# de0_expansion.net
KiCad netlist of a schematic drawn in EAGLE
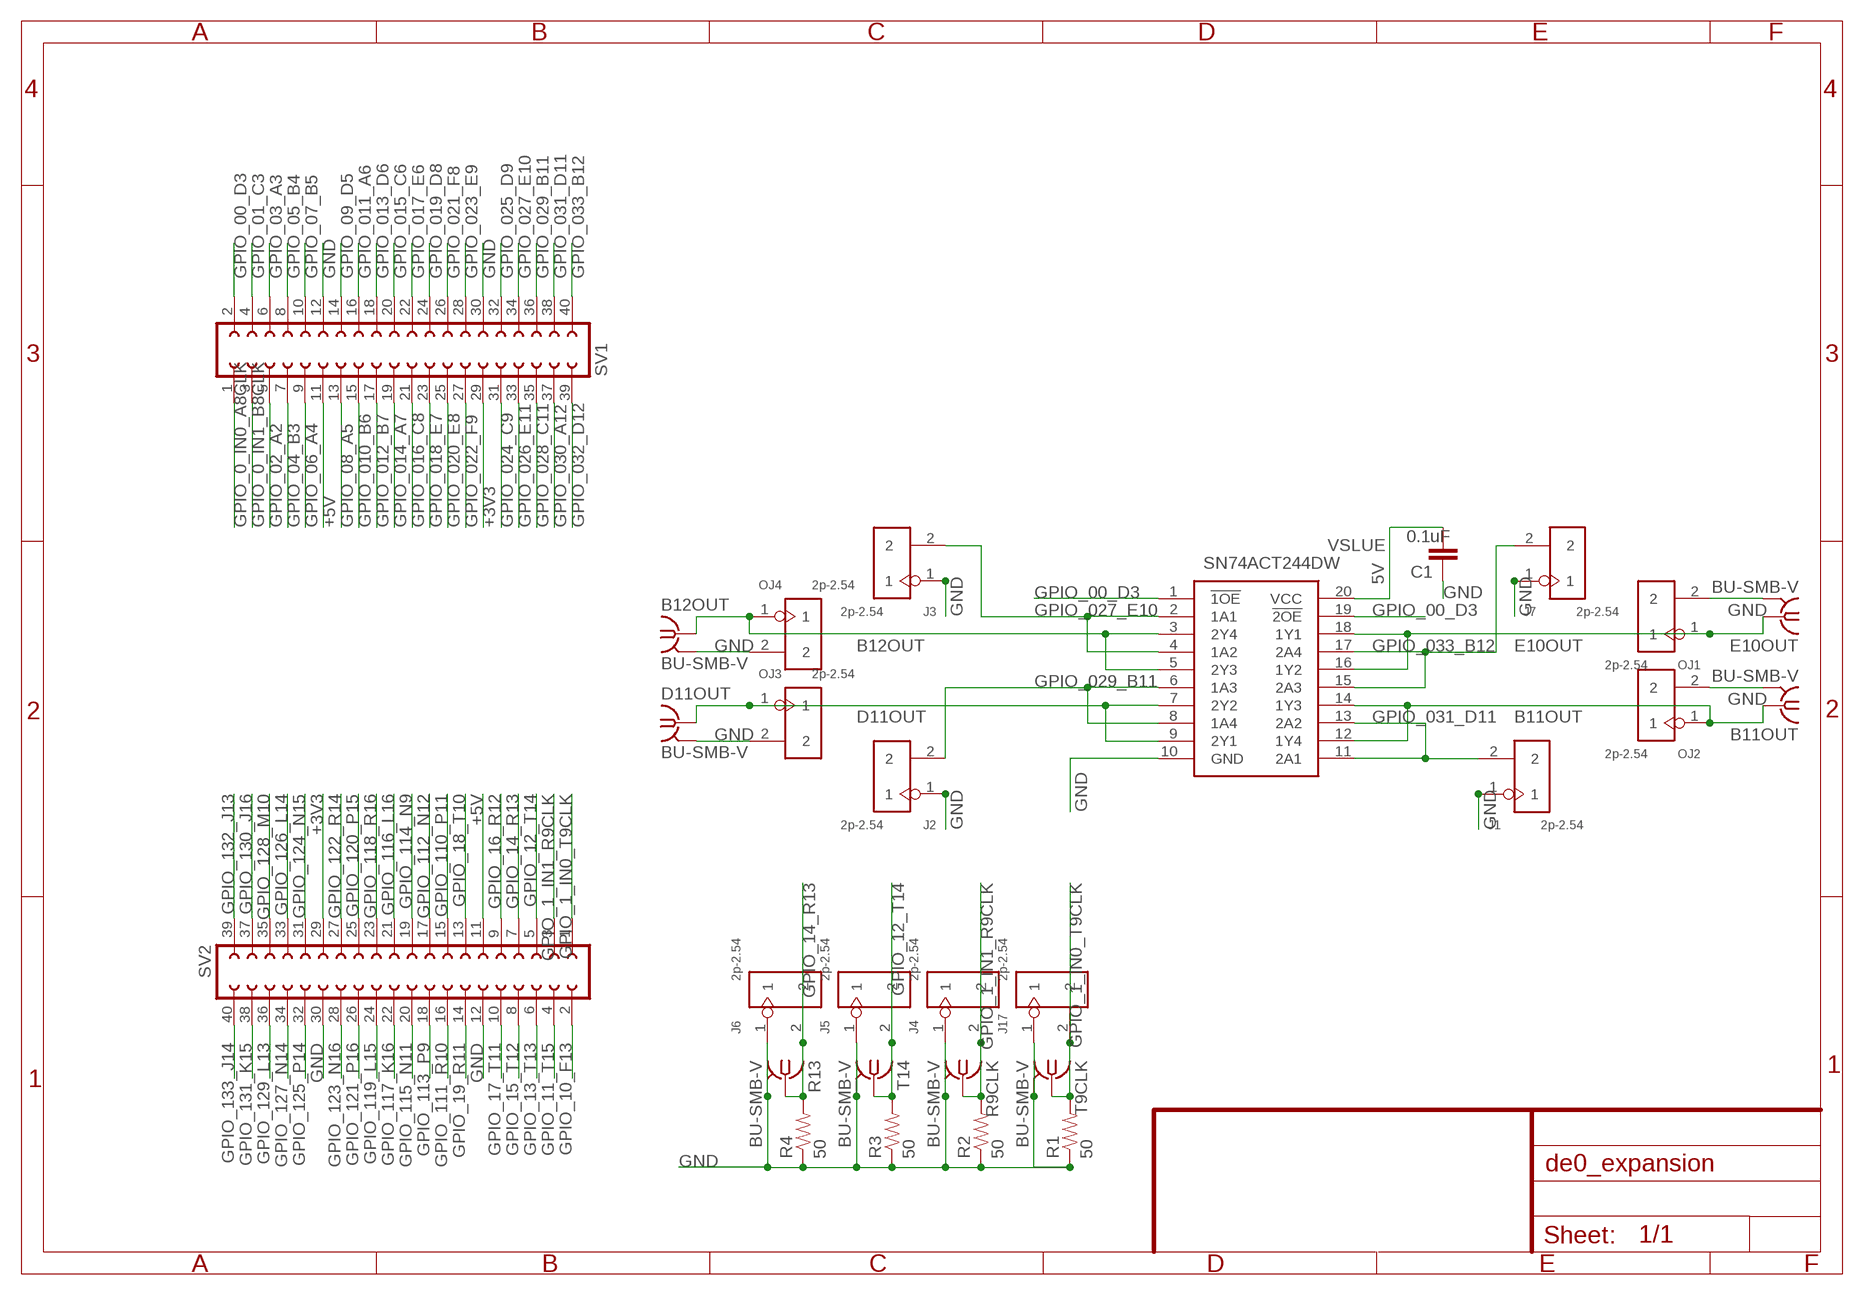
[diagram p0: schematic, sheet 1]

(export (version "E")
  (design (tool "Eeschema 10.0.6"))
  (components
    (comp (ref "B11OUT")
      (value "BU-SMB-V")
      (footprint "eagle-import:BU-SMB-V")
      (libsource (lib "eagle-import") (part "BU-SMB-V"))
    )
    (comp (ref "B12OUT")
      (value "BU-SMB-V")
      (footprint "eagle-import:BU-SMB-V")
      (libsource (lib "eagle-import") (part "BU-SMB-V"))
    )
    (comp (ref "C1")
      (value "0.1uF")
      (footprint "eagle-import:0805")
      (libsource (lib "eagle-import") (part "CAP0805"))
    )
    (comp (ref "D11OUT")
      (value "BU-SMB-V")
      (footprint "eagle-import:BU-SMB-V")
      (libsource (lib "eagle-import") (part "BU-SMB-V"))
    )
    (comp (ref "E10OUT")
      (value "BU-SMB-V")
      (footprint "eagle-import:BU-SMB-V")
      (libsource (lib "eagle-import") (part "BU-SMB-V"))
    )
    (comp (ref "J1")
      (value "2p-2.54")
      (footprint "eagle-import:H2-2.54")
      (fields (field (name "MPN") "P125-1102A0BS116A1"))
      (libsource (lib "eagle-import") (part "DIP-BLACK-MALE-HEADER-VERT(2P-2.54)"))
    )
    (comp (ref "J2")
      (value "2p-2.54")
      (footprint "eagle-import:H2-2.54")
      (fields (field (name "MPN") "P125-1102A0BS116A1"))
      (libsource (lib "eagle-import") (part "DIP-BLACK-MALE-HEADER-VERT(2P-2.54)"))
    )
    (comp (ref "J3")
      (value "2p-2.54")
      (footprint "eagle-import:H2-2.54")
      (fields (field (name "MPN") "P125-1102A0BS116A1"))
      (libsource (lib "eagle-import") (part "DIP-BLACK-MALE-HEADER-VERT(2P-2.54)"))
    )
    (comp (ref "J4")
      (value "2p-2.54")
      (footprint "eagle-import:H2-2.54")
      (fields (field (name "MPN") "P125-1102A0BS116A1"))
      (libsource (lib "eagle-import") (part "DIP-BLACK-MALE-HEADER-VERT(2P-2.54)"))
    )
    (comp (ref "J5")
      (value "2p-2.54")
      (footprint "eagle-import:H2-2.54")
      (fields (field (name "MPN") "P125-1102A0BS116A1"))
      (libsource (lib "eagle-import") (part "DIP-BLACK-MALE-HEADER-VERT(2P-2.54)"))
    )
    (comp (ref "J6")
      (value "2p-2.54")
      (footprint "eagle-import:H2-2.54")
      (fields (field (name "MPN") "P125-1102A0BS116A1"))
      (libsource (lib "eagle-import") (part "DIP-BLACK-MALE-HEADER-VERT(2P-2.54)"))
    )
    (comp (ref "J7")
      (value "2p-2.54")
      (footprint "eagle-import:H2-2.54")
      (fields (field (name "MPN") "P125-1102A0BS116A1"))
      (libsource (lib "eagle-import") (part "DIP-BLACK-MALE-HEADER-VERT(2P-2.54)"))
    )
    (comp (ref "J17")
      (value "2p-2.54")
      (footprint "eagle-import:H2-2.54")
      (fields (field (name "MPN") "P125-1102A0BS116A1"))
      (libsource (lib "eagle-import") (part "DIP-BLACK-MALE-HEADER-VERT(2P-2.54)"))
    )
    (comp (ref "OJ1")
      (value "2p-2.54")
      (footprint "eagle-import:H2-2.54")
      (fields (field (name "MPN") "P125-1102A0BS116A1"))
      (libsource (lib "eagle-import") (part "DIP-BLACK-MALE-HEADER-VERT(2P-2.54)"))
    )
    (comp (ref "OJ2")
      (value "2p-2.54")
      (footprint "eagle-import:H2-2.54")
      (fields (field (name "MPN") "P125-1102A0BS116A1"))
      (libsource (lib "eagle-import") (part "DIP-BLACK-MALE-HEADER-VERT(2P-2.54)"))
    )
    (comp (ref "OJ3")
      (value "2p-2.54")
      (footprint "eagle-import:H2-2.54")
      (fields (field (name "MPN") "P125-1102A0BS116A1"))
      (libsource (lib "eagle-import") (part "DIP-BLACK-MALE-HEADER-VERT(2P-2.54)"))
    )
    (comp (ref "OJ4")
      (value "2p-2.54")
      (footprint "eagle-import:H2-2.54")
      (fields (field (name "MPN") "P125-1102A0BS116A1"))
      (libsource (lib "eagle-import") (part "DIP-BLACK-MALE-HEADER-VERT(2P-2.54)"))
    )
    (comp (ref "R1")
      (value "50")
      (footprint "eagle-import:AXIAL-0.3")
      (libsource (lib "eagle-import") (part "RESISTORAXIAL-0.3"))
    )
    (comp (ref "R2")
      (value "50")
      (footprint "eagle-import:AXIAL-0.3")
      (libsource (lib "eagle-import") (part "RESISTORAXIAL-0.3"))
    )
    (comp (ref "R3")
      (value "50")
      (footprint "eagle-import:AXIAL-0.3")
      (libsource (lib "eagle-import") (part "RESISTORAXIAL-0.3"))
    )
    (comp (ref "R4")
      (value "50")
      (footprint "eagle-import:AXIAL-0.3")
      (libsource (lib "eagle-import") (part "RESISTORAXIAL-0.3"))
    )
    (comp (ref "R9CLK")
      (value "BU-SMB-V")
      (footprint "eagle-import:BU-SMB-V")
      (libsource (lib "eagle-import") (part "BU-SMB-V"))
    )
    (comp (ref "R13")
      (value "BU-SMB-V")
      (footprint "eagle-import:BU-SMB-V")
      (libsource (lib "eagle-import") (part "BU-SMB-V"))
    )
    (comp (ref "SV1")
      (value "FE20-2")
      (footprint "eagle-import:FE20-2")
      (libsource (lib "eagle-import") (part "FE20-2"))
    )
    (comp (ref "SV2")
      (value "FE20-2")
      (footprint "eagle-import:FE20-2")
      (libsource (lib "eagle-import") (part "FE20-2"))
    )
    (comp (ref "T9CLK")
      (value "BU-SMB-V")
      (footprint "eagle-import:BU-SMB-V")
      (libsource (lib "eagle-import") (part "BU-SMB-V"))
    )
    (comp (ref "T14")
      (value "BU-SMB-V")
      (footprint "eagle-import:BU-SMB-V")
      (libsource (lib "eagle-import") (part "BU-SMB-V"))
    )
    (comp (ref "VSLUE")
      (value "SN74ACT244DW")
      (footprint "eagle-import:SOIC127P1030X265-20N")
      (fields (field (name "RS_PART_NUMBER") "4363169"))
      (libsource (lib "eagle-import") (part "SN74ACT244DW"))
    )
  )
  (nets
    (net (code "1") (name "/+3V3") (class "Default")
      (node (ref "SV1") (pin "29") (pinfunction "29_29") (pintype "passive"))
      (node (ref "SV2") (pin "29") (pinfunction "29_29") (pintype "passive"))
    )
    (net (code "2") (name "/+5V") (class "Default")
      (node (ref "SV1") (pin "11") (pinfunction "11_11") (pintype "passive"))
      (node (ref "SV2") (pin "11") (pinfunction "11_11") (pintype "passive"))
    )
    (net (code "3") (name "/5V") (class "Default")
      (node (ref "C1") (pin "2") (pinfunction "2_2") (pintype "passive"))
      (node (ref "VSLUE") (pin "20") (pinfunction "VCC_20") (pintype "power_in"))
    )
    (net (code "4") (name "/B11OUT") (class "Default")
      (node (ref "B11OUT") (pin "1") (pinfunction "1_1") (pintype "passive"))
      (node (ref "OJ2") (pin "1") (pinfunction "1_1") (pintype "bidirectional"))
      (node (ref "VSLUE") (pin "12") (pinfunction "1Y4_12") (pintype "output"))
      (node (ref "VSLUE") (pin "14") (pinfunction "1Y3_14") (pintype "output"))
    )
    (net (code "5") (name "/B12OUT") (class "Default")
      (node (ref "B12OUT") (pin "1") (pinfunction "1_1") (pintype "passive"))
      (node (ref "OJ4") (pin "1") (pinfunction "1_1") (pintype "bidirectional"))
      (node (ref "VSLUE") (pin "3") (pinfunction "2Y4_3") (pintype "output"))
      (node (ref "VSLUE") (pin "5") (pinfunction "2Y3_5") (pintype "output"))
    )
    (net (code "6") (name "/D11OUT") (class "Default")
      (node (ref "D11OUT") (pin "1") (pinfunction "1_1") (pintype "passive"))
      (node (ref "OJ3") (pin "1") (pinfunction "1_1") (pintype "bidirectional"))
      (node (ref "VSLUE") (pin "7") (pinfunction "2Y2_7") (pintype "output"))
      (node (ref "VSLUE") (pin "9") (pinfunction "2Y1_9") (pintype "output"))
    )
    (net (code "7") (name "/E10OUT") (class "Default")
      (node (ref "E10OUT") (pin "1") (pinfunction "1_1") (pintype "passive"))
      (node (ref "OJ1") (pin "1") (pinfunction "1_1") (pintype "bidirectional"))
      (node (ref "VSLUE") (pin "16") (pinfunction "1Y2_16") (pintype "output"))
      (node (ref "VSLUE") (pin "18") (pinfunction "1Y1_18") (pintype "output"))
    )
    (net (code "8") (name "/GND") (class "Default")
      (node (ref "B11OUT") (pin "2") (pinfunction "2_2") (pintype "passive"))
      (node (ref "B11OUT") (pin "3") (pinfunction "2_3") (pintype "passive"))
      (node (ref "B11OUT") (pin "4") (pinfunction "2_4") (pintype "passive"))
      (node (ref "B11OUT") (pin "5") (pinfunction "2_5") (pintype "passive"))
      (node (ref "B12OUT") (pin "2") (pinfunction "2_2") (pintype "passive"))
      (node (ref "B12OUT") (pin "3") (pinfunction "2_3") (pintype "passive"))
      (node (ref "B12OUT") (pin "4") (pinfunction "2_4") (pintype "passive"))
      (node (ref "B12OUT") (pin "5") (pinfunction "2_5") (pintype "passive"))
      (node (ref "C1") (pin "1") (pinfunction "1_1") (pintype "passive"))
      (node (ref "D11OUT") (pin "2") (pinfunction "2_2") (pintype "passive"))
      (node (ref "D11OUT") (pin "3") (pinfunction "2_3") (pintype "passive"))
      (node (ref "D11OUT") (pin "4") (pinfunction "2_4") (pintype "passive"))
      (node (ref "D11OUT") (pin "5") (pinfunction "2_5") (pintype "passive"))
      (node (ref "E10OUT") (pin "2") (pinfunction "2_2") (pintype "passive"))
      (node (ref "E10OUT") (pin "3") (pinfunction "2_3") (pintype "passive"))
      (node (ref "E10OUT") (pin "4") (pinfunction "2_4") (pintype "passive"))
      (node (ref "E10OUT") (pin "5") (pinfunction "2_5") (pintype "passive"))
      (node (ref "J1") (pin "1") (pinfunction "1_1") (pintype "bidirectional"))
      (node (ref "J17") (pin "1") (pinfunction "1_1") (pintype "bidirectional"))
      (node (ref "J2") (pin "1") (pinfunction "1_1") (pintype "bidirectional"))
      (node (ref "J3") (pin "1") (pinfunction "1_1") (pintype "bidirectional"))
      (node (ref "J4") (pin "1") (pinfunction "1_1") (pintype "bidirectional"))
      (node (ref "J5") (pin "1") (pinfunction "1_1") (pintype "bidirectional"))
      (node (ref "J6") (pin "1") (pinfunction "1_1") (pintype "bidirectional"))
      (node (ref "J7") (pin "1") (pinfunction "1_1") (pintype "bidirectional"))
      (node (ref "OJ1") (pin "2") (pinfunction "2_2") (pintype "bidirectional"))
      (node (ref "OJ2") (pin "2") (pinfunction "2_2") (pintype "bidirectional"))
      (node (ref "OJ3") (pin "2") (pinfunction "2_2") (pintype "bidirectional"))
      (node (ref "OJ4") (pin "2") (pinfunction "2_2") (pintype "bidirectional"))
      (node (ref "R1") (pin "P$1") (pinfunction "1_P$1") (pintype "passive"))
      (node (ref "R13") (pin "2") (pinfunction "2_2") (pintype "passive"))
      (node (ref "R13") (pin "3") (pinfunction "2_3") (pintype "passive"))
      (node (ref "R13") (pin "4") (pinfunction "2_4") (pintype "passive"))
      (node (ref "R13") (pin "5") (pinfunction "2_5") (pintype "passive"))
      (node (ref "R2") (pin "P$1") (pinfunction "1_P$1") (pintype "passive"))
      (node (ref "R3") (pin "P$1") (pinfunction "1_P$1") (pintype "passive"))
      (node (ref "R4") (pin "P$1") (pinfunction "1_P$1") (pintype "passive"))
      (node (ref "R9CLK") (pin "2") (pinfunction "2_2") (pintype "passive"))
      (node (ref "R9CLK") (pin "3") (pinfunction "2_3") (pintype "passive"))
      (node (ref "R9CLK") (pin "4") (pinfunction "2_4") (pintype "passive"))
      (node (ref "R9CLK") (pin "5") (pinfunction "2_5") (pintype "passive"))
      (node (ref "SV1") (pin "12") (pinfunction "12_12") (pintype "passive"))
      (node (ref "SV1") (pin "30") (pinfunction "30_30") (pintype "passive"))
      (node (ref "SV2") (pin "12") (pinfunction "12_12") (pintype "passive"))
      (node (ref "SV2") (pin "30") (pinfunction "30_30") (pintype "passive"))
      (node (ref "T14") (pin "2") (pinfunction "2_2") (pintype "passive"))
      (node (ref "T14") (pin "3") (pinfunction "2_3") (pintype "passive"))
      (node (ref "T14") (pin "4") (pinfunction "2_4") (pintype "passive"))
      (node (ref "T14") (pin "5") (pinfunction "2_5") (pintype "passive"))
      (node (ref "T9CLK") (pin "2") (pinfunction "2_2") (pintype "passive"))
      (node (ref "T9CLK") (pin "3") (pinfunction "2_3") (pintype "passive"))
      (node (ref "T9CLK") (pin "4") (pinfunction "2_4") (pintype "passive"))
      (node (ref "T9CLK") (pin "5") (pinfunction "2_5") (pintype "passive"))
      (node (ref "VSLUE") (pin "10") (pinfunction "GND_10") (pintype "power_in"))
    )
    (net (code "9") (name "/GPIO_00_D3") (class "Default")
      (node (ref "SV1") (pin "2") (pinfunction "2_2") (pintype "passive"))
      (node (ref "VSLUE") (pin "1") (pinfunction "~{1OE}_1") (pintype "input"))
      (node (ref "VSLUE") (pin "19") (pinfunction "~{2OE}_19") (pintype "input"))
    )
    (net (code "10") (name "/GPIO_0_IN0_A8CLK") (class "Default")
      (node (ref "SV1") (pin "1") (pinfunction "1_1") (pintype "passive"))
    )
    (net (code "11") (name "/GPIO_0_IN1_B8CLK") (class "Default")
      (node (ref "SV1") (pin "3") (pinfunction "3_3") (pintype "passive"))
    )
    (net (code "12") (name "/GPIO_01_C3") (class "Default")
      (node (ref "SV1") (pin "4") (pinfunction "4_4") (pintype "passive"))
    )
    (net (code "13") (name "/GPIO_1_IN0_T9CLK") (class "Default")
      (node (ref "J17") (pin "2") (pinfunction "2_2") (pintype "bidirectional"))
      (node (ref "R1") (pin "P$2") (pinfunction "2_P$2") (pintype "passive"))
      (node (ref "SV2") (pin "1") (pinfunction "1_1") (pintype "passive"))
      (node (ref "T9CLK") (pin "1") (pinfunction "1_1") (pintype "passive"))
    )
    (net (code "14") (name "/GPIO_1_IN1_R9CLK") (class "Default")
      (node (ref "J4") (pin "2") (pinfunction "2_2") (pintype "bidirectional"))
      (node (ref "R2") (pin "P$2") (pinfunction "2_P$2") (pintype "passive"))
      (node (ref "R9CLK") (pin "1") (pinfunction "1_1") (pintype "passive"))
      (node (ref "SV2") (pin "3") (pinfunction "3_3") (pintype "passive"))
    )
    (net (code "15") (name "/GPIO_02_A2") (class "Default")
      (node (ref "SV1") (pin "5") (pinfunction "5_5") (pintype "passive"))
    )
    (net (code "16") (name "/GPIO_03_A3") (class "Default")
      (node (ref "SV1") (pin "6") (pinfunction "6_6") (pintype "passive"))
    )
    (net (code "17") (name "/GPIO_04_B3") (class "Default")
      (node (ref "SV1") (pin "7") (pinfunction "7_7") (pintype "passive"))
    )
    (net (code "18") (name "/GPIO_05_B4") (class "Default")
      (node (ref "SV1") (pin "8") (pinfunction "8_8") (pintype "passive"))
    )
    (net (code "19") (name "/GPIO_06_A4") (class "Default")
      (node (ref "SV1") (pin "9") (pinfunction "9_9") (pintype "passive"))
    )
    (net (code "20") (name "/GPIO_07_B5") (class "Default")
      (node (ref "SV1") (pin "10") (pinfunction "10_10") (pintype "passive"))
    )
    (net (code "21") (name "/GPIO_08_A5") (class "Default")
      (node (ref "SV1") (pin "13") (pinfunction "13_13") (pintype "passive"))
    )
    (net (code "22") (name "/GPIO_09_D5") (class "Default")
      (node (ref "SV1") (pin "14") (pinfunction "14_14") (pintype "passive"))
    )
    (net (code "23") (name "/GPIO_010_B6") (class "Default")
      (node (ref "SV1") (pin "15") (pinfunction "15_15") (pintype "passive"))
    )
    (net (code "24") (name "/GPIO_10_F13") (class "Default")
      (node (ref "SV2") (pin "2") (pinfunction "2_2") (pintype "passive"))
    )
    (net (code "25") (name "/GPIO_011_A6") (class "Default")
      (node (ref "SV1") (pin "16") (pinfunction "16_16") (pintype "passive"))
    )
    (net (code "26") (name "/GPIO_11_T15") (class "Default")
      (node (ref "SV2") (pin "4") (pinfunction "4_4") (pintype "passive"))
    )
    (net (code "27") (name "/GPIO_012_B7") (class "Default")
      (node (ref "SV1") (pin "17") (pinfunction "17_17") (pintype "passive"))
    )
    (net (code "28") (name "/GPIO_12_T14") (class "Default")
      (node (ref "J5") (pin "2") (pinfunction "2_2") (pintype "bidirectional"))
      (node (ref "R3") (pin "P$2") (pinfunction "2_P$2") (pintype "passive"))
      (node (ref "SV2") (pin "5") (pinfunction "5_5") (pintype "passive"))
      (node (ref "T14") (pin "1") (pinfunction "1_1") (pintype "passive"))
    )
    (net (code "29") (name "/GPIO_013_D6") (class "Default")
      (node (ref "SV1") (pin "18") (pinfunction "18_18") (pintype "passive"))
    )
    (net (code "30") (name "/GPIO_13_T13") (class "Default")
      (node (ref "SV2") (pin "6") (pinfunction "6_6") (pintype "passive"))
    )
    (net (code "31") (name "/GPIO_014_A7") (class "Default")
      (node (ref "SV1") (pin "19") (pinfunction "19_19") (pintype "passive"))
    )
    (net (code "32") (name "/GPIO_14_R13") (class "Default")
      (node (ref "J6") (pin "2") (pinfunction "2_2") (pintype "bidirectional"))
      (node (ref "R13") (pin "1") (pinfunction "1_1") (pintype "passive"))
      (node (ref "R4") (pin "P$2") (pinfunction "2_P$2") (pintype "passive"))
      (node (ref "SV2") (pin "7") (pinfunction "7_7") (pintype "passive"))
    )
    (net (code "33") (name "/GPIO_015_C6") (class "Default")
      (node (ref "SV1") (pin "20") (pinfunction "20_20") (pintype "passive"))
    )
    (net (code "34") (name "/GPIO_15_T12") (class "Default")
      (node (ref "SV2") (pin "8") (pinfunction "8_8") (pintype "passive"))
    )
    (net (code "35") (name "/GPIO_016_C8") (class "Default")
      (node (ref "SV1") (pin "21") (pinfunction "21_21") (pintype "passive"))
    )
    (net (code "36") (name "/GPIO_16_R12") (class "Default")
      (node (ref "SV2") (pin "9") (pinfunction "9_9") (pintype "passive"))
    )
    (net (code "37") (name "/GPIO_017_E6") (class "Default")
      (node (ref "SV1") (pin "22") (pinfunction "22_22") (pintype "passive"))
    )
    (net (code "38") (name "/GPIO_17_T11") (class "Default")
      (node (ref "SV2") (pin "10") (pinfunction "10_10") (pintype "passive"))
    )
    (net (code "39") (name "/GPIO_018_E7") (class "Default")
      (node (ref "SV1") (pin "23") (pinfunction "23_23") (pintype "passive"))
    )
    (net (code "40") (name "/GPIO_18_T10") (class "Default")
      (node (ref "SV2") (pin "13") (pinfunction "13_13") (pintype "passive"))
    )
    (net (code "41") (name "/GPIO_019_D8") (class "Default")
      (node (ref "SV1") (pin "24") (pinfunction "24_24") (pintype "passive"))
    )
    (net (code "42") (name "/GPIO_19_R11") (class "Default")
      (node (ref "SV2") (pin "14") (pinfunction "14_14") (pintype "passive"))
    )
    (net (code "43") (name "/GPIO_020_E8") (class "Default")
      (node (ref "SV1") (pin "25") (pinfunction "25_25") (pintype "passive"))
    )
    (net (code "44") (name "/GPIO_021_F8") (class "Default")
      (node (ref "SV1") (pin "26") (pinfunction "26_26") (pintype "passive"))
    )
    (net (code "45") (name "/GPIO_022_F9") (class "Default")
      (node (ref "SV1") (pin "27") (pinfunction "27_27") (pintype "passive"))
    )
    (net (code "46") (name "/GPIO_023_E9") (class "Default")
      (node (ref "SV1") (pin "28") (pinfunction "28_28") (pintype "passive"))
    )
    (net (code "47") (name "/GPIO_024_C9") (class "Default")
      (node (ref "SV1") (pin "31") (pinfunction "31_31") (pintype "passive"))
    )
    (net (code "48") (name "/GPIO_025_D9") (class "Default")
      (node (ref "SV1") (pin "32") (pinfunction "32_32") (pintype "passive"))
    )
    (net (code "49") (name "/GPIO_026_E11") (class "Default")
      (node (ref "SV1") (pin "33") (pinfunction "33_33") (pintype "passive"))
    )
    (net (code "50") (name "/GPIO_027_E10") (class "Default")
      (node (ref "J3") (pin "2") (pinfunction "2_2") (pintype "bidirectional"))
      (node (ref "SV1") (pin "34") (pinfunction "34_34") (pintype "passive"))
      (node (ref "VSLUE") (pin "2") (pinfunction "1A1_2") (pintype "input"))
      (node (ref "VSLUE") (pin "4") (pinfunction "1A2_4") (pintype "input"))
    )
    (net (code "51") (name "/GPIO_028_C11") (class "Default")
      (node (ref "SV1") (pin "35") (pinfunction "35_35") (pintype "passive"))
    )
    (net (code "52") (name "/GPIO_029_B11") (class "Default")
      (node (ref "J2") (pin "2") (pinfunction "2_2") (pintype "bidirectional"))
      (node (ref "SV1") (pin "36") (pinfunction "36_36") (pintype "passive"))
      (node (ref "VSLUE") (pin "6") (pinfunction "1A3_6") (pintype "input"))
      (node (ref "VSLUE") (pin "8") (pinfunction "1A4_8") (pintype "input"))
    )
    (net (code "53") (name "/GPIO_030_A12") (class "Default")
      (node (ref "SV1") (pin "37") (pinfunction "37_37") (pintype "passive"))
    )
    (net (code "54") (name "/GPIO_031_D11") (class "Default")
      (node (ref "J1") (pin "2") (pinfunction "2_2") (pintype "bidirectional"))
      (node (ref "SV1") (pin "38") (pinfunction "38_38") (pintype "passive"))
      (node (ref "VSLUE") (pin "11") (pinfunction "2A1_11") (pintype "input"))
      (node (ref "VSLUE") (pin "13") (pinfunction "2A2_13") (pintype "input"))
    )
    (net (code "55") (name "/GPIO_032_D12") (class "Default")
      (node (ref "SV1") (pin "39") (pinfunction "39_39") (pintype "passive"))
    )
    (net (code "56") (name "/GPIO_033_B12") (class "Default")
      (node (ref "J7") (pin "2") (pinfunction "2_2") (pintype "bidirectional"))
      (node (ref "SV1") (pin "40") (pinfunction "40_40") (pintype "passive"))
      (node (ref "VSLUE") (pin "15") (pinfunction "2A3_15") (pintype "input"))
      (node (ref "VSLUE") (pin "17") (pinfunction "2A4_17") (pintype "input"))
    )
    (net (code "57") (name "/GPIO_110_P11") (class "Default")
      (node (ref "SV2") (pin "15") (pinfunction "15_15") (pintype "passive"))
    )
    (net (code "58") (name "/GPIO_111_R10") (class "Default")
      (node (ref "SV2") (pin "16") (pinfunction "16_16") (pintype "passive"))
    )
    (net (code "59") (name "/GPIO_112_N12") (class "Default")
      (node (ref "SV2") (pin "17") (pinfunction "17_17") (pintype "passive"))
    )
    (net (code "60") (name "/GPIO_113_P9") (class "Default")
      (node (ref "SV2") (pin "18") (pinfunction "18_18") (pintype "passive"))
    )
    (net (code "61") (name "/GPIO_114_N9") (class "Default")
      (node (ref "SV2") (pin "19") (pinfunction "19_19") (pintype "passive"))
    )
    (net (code "62") (name "/GPIO_115_N11") (class "Default")
      (node (ref "SV2") (pin "20") (pinfunction "20_20") (pintype "passive"))
    )
    (net (code "63") (name "/GPIO_116_L16") (class "Default")
      (node (ref "SV2") (pin "21") (pinfunction "21_21") (pintype "passive"))
    )
    (net (code "64") (name "/GPIO_117_K16") (class "Default")
      (node (ref "SV2") (pin "22") (pinfunction "22_22") (pintype "passive"))
    )
    (net (code "65") (name "/GPIO_118_R16") (class "Default")
      (node (ref "SV2") (pin "23") (pinfunction "23_23") (pintype "passive"))
    )
    (net (code "66") (name "/GPIO_119_L15") (class "Default")
      (node (ref "SV2") (pin "24") (pinfunction "24_24") (pintype "passive"))
    )
    (net (code "67") (name "/GPIO_120_P15") (class "Default")
      (node (ref "SV2") (pin "25") (pinfunction "25_25") (pintype "passive"))
    )
    (net (code "68") (name "/GPIO_121_P16") (class "Default")
      (node (ref "SV2") (pin "26") (pinfunction "26_26") (pintype "passive"))
    )
    (net (code "69") (name "/GPIO_122_R14") (class "Default")
      (node (ref "SV2") (pin "27") (pinfunction "27_27") (pintype "passive"))
    )
    (net (code "70") (name "/GPIO_123_N16") (class "Default")
      (node (ref "SV2") (pin "28") (pinfunction "28_28") (pintype "passive"))
    )
    (net (code "71") (name "/GPIO_124_N15") (class "Default")
      (node (ref "SV2") (pin "31") (pinfunction "31_31") (pintype "passive"))
    )
    (net (code "72") (name "/GPIO_125_P14") (class "Default")
      (node (ref "SV2") (pin "32") (pinfunction "32_32") (pintype "passive"))
    )
    (net (code "73") (name "/GPIO_126_L14") (class "Default")
      (node (ref "SV2") (pin "33") (pinfunction "33_33") (pintype "passive"))
    )
    (net (code "74") (name "/GPIO_127_N14") (class "Default")
      (node (ref "SV2") (pin "34") (pinfunction "34_34") (pintype "passive"))
    )
    (net (code "75") (name "/GPIO_128_M10") (class "Default")
      (node (ref "SV2") (pin "35") (pinfunction "35_35") (pintype "passive"))
    )
    (net (code "76") (name "/GPIO_129_L13") (class "Default")
      (node (ref "SV2") (pin "36") (pinfunction "36_36") (pintype "passive"))
    )
    (net (code "77") (name "/GPIO_130_J16") (class "Default")
      (node (ref "SV2") (pin "37") (pinfunction "37_37") (pintype "passive"))
    )
    (net (code "78") (name "/GPIO_131_K15") (class "Default")
      (node (ref "SV2") (pin "38") (pinfunction "38_38") (pintype "passive"))
    )
    (net (code "79") (name "/GPIO_132_J13") (class "Default")
      (node (ref "SV2") (pin "39") (pinfunction "39_39") (pintype "passive"))
    )
    (net (code "80") (name "/GPIO_133_J14") (class "Default")
      (node (ref "SV2") (pin "40") (pinfunction "40_40") (pintype "passive"))
    )
  )
)
